# probe.net
KiCad netlist of a schematic drawn in Altium Designer
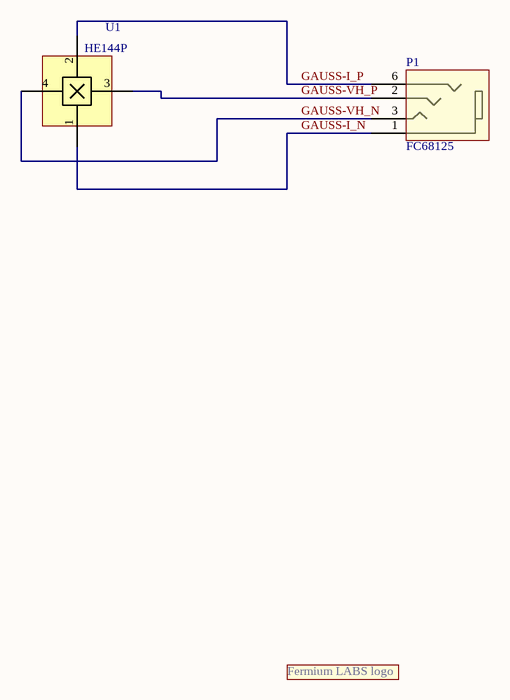
[diagram p0: probe.SchDoc]

(export (version "E")
  (design (tool "Eeschema 10.0.6"))
  (components
    (comp (ref "logo")
      (value "fermiumlabs-logo")
      (footprint "frm-med")
      (libsource (lib "custom_components") (part "fermiumlabs-logo"))
    )
    (comp (ref "P1")
      (value "~")
      (footprint "custom_components:FC68125")
      (fields
        (field (name "SUPPLIER PART NUMBER 1") "FC68125")
        (field (name "MANUFACTURER") "CLIFF")
        (field (name "MANUFACTURER PART NUMBER") "FC68125")
      )
      (libsource (lib "custom_components") (part "FC68125"))
    )
    (comp (ref "U1")
      (value "~")
      (footprint "custom_components:HE144P-buried")
      (fields (field (name "MANUFACTURER") "Asensor") (field (name "MANUFACTURER PART NUMBER") "HE144P"))
      (libsource (lib "custom_components") (part "he144p"))
    )
  )
  (nets
    (net (code "1") (name "/GAUSS-I_N") (class "Default")
      (node (ref "P1") (pin "1") (pinfunction "1_1") (pintype "passive"))
      (node (ref "U1") (pin "1") (pinfunction "1_1") (pintype "passive"))
    )
    (net (code "2") (name "/GAUSS-I_P") (class "Default")
      (node (ref "P1") (pin "6") (pinfunction "6_6") (pintype "passive"))
      (node (ref "U1") (pin "2") (pinfunction "2_2") (pintype "passive"))
    )
    (net (code "3") (name "/GAUSS-VH_N") (class "Default")
      (node (ref "P1") (pin "3") (pinfunction "3_3") (pintype "passive"))
      (node (ref "U1") (pin "4") (pinfunction "4_4") (pintype "passive"))
    )
    (net (code "4") (name "/GAUSS-VH_P") (class "Default")
      (node (ref "P1") (pin "2") (pinfunction "2_2") (pintype "passive"))
      (node (ref "U1") (pin "3") (pinfunction "3_3") (pintype "passive"))
    )
  )
)
